# MAGNEBOT2.net
KiCad netlist of a schematic drawn in EAGLE
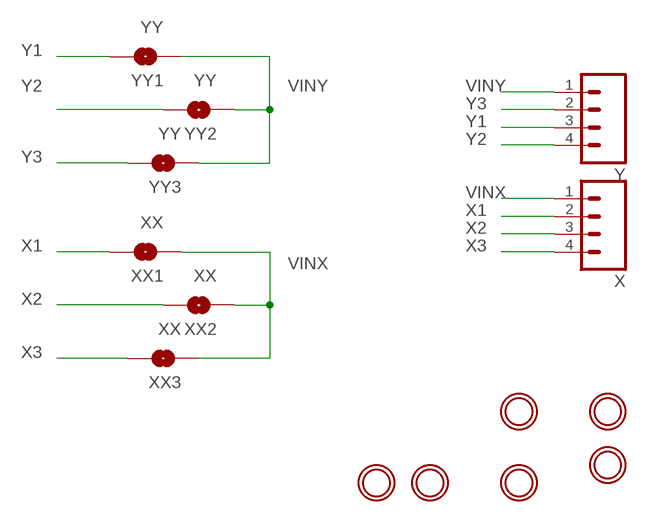
[diagram p0: schematic, sheet 1]

(export (version "E")
  (design (tool "Eeschema 10.0.6"))
  (components
    (comp (ref "U$1")
      (value "MOUNTINGHOLE2.0")
      (footprint "eagle-import:MOUNTINGHOLE_2.0_PLATED")
      (libsource (lib "eagle-import") (part "MOUNTINGHOLE2.0"))
    )
    (comp (ref "U$2")
      (value "MOUNTINGHOLE2.0")
      (footprint "eagle-import:MOUNTINGHOLE_2.0_PLATED")
      (libsource (lib "eagle-import") (part "MOUNTINGHOLE2.0"))
    )
    (comp (ref "U$3")
      (value "MOUNTINGHOLE2.0")
      (footprint "eagle-import:MOUNTINGHOLE_2.0_PLATED")
      (libsource (lib "eagle-import") (part "MOUNTINGHOLE2.0"))
    )
    (comp (ref "U$4")
      (value "MOUNTINGHOLE2.0")
      (footprint "eagle-import:MOUNTINGHOLE_2.0_PLATED")
      (libsource (lib "eagle-import") (part "MOUNTINGHOLE2.0"))
    )
    (comp (ref "U$5")
      (value "MOUNTINGHOLE2.0")
      (footprint "eagle-import:MOUNTINGHOLE_2.0_PLATED")
      (libsource (lib "eagle-import") (part "MOUNTINGHOLE2.0"))
    )
    (comp (ref "U$10")
      (value "MOUNTINGHOLE2.0")
      (footprint "eagle-import:MOUNTINGHOLE_2.0_PLATED")
      (libsource (lib "eagle-import") (part "MOUNTINGHOLE2.0"))
    )
    (comp (ref "X")
      (value "M04PTH")
      (footprint "eagle-import:1X04")
      (libsource (lib "eagle-import") (part "M04PTH"))
    )
    (comp (ref "XX1")
      (value "XX")
      (footprint "eagle-import:SJ_2S-TRACE")
      (libsource (lib "eagle-import") (part "SOLDERJUMPERTRACE"))
    )
    (comp (ref "XX2")
      (value "XX")
      (footprint "eagle-import:SJ_2S-TRACE")
      (libsource (lib "eagle-import") (part "SOLDERJUMPERTRACE"))
    )
    (comp (ref "XX3")
      (value "XX")
      (footprint "eagle-import:SJ_2S-TRACE")
      (libsource (lib "eagle-import") (part "SOLDERJUMPERTRACE"))
    )
    (comp (ref "Y")
      (value "M04PTH")
      (footprint "eagle-import:1X04")
      (libsource (lib "eagle-import") (part "M04PTH"))
    )
    (comp (ref "YY1")
      (value "YY")
      (footprint "eagle-import:SJ_2S-TRACE")
      (libsource (lib "eagle-import") (part "SOLDERJUMPERTRACE"))
    )
    (comp (ref "YY2")
      (value "YY")
      (footprint "eagle-import:SJ_2S-TRACE")
      (libsource (lib "eagle-import") (part "SOLDERJUMPERTRACE"))
    )
    (comp (ref "YY3")
      (value "YY")
      (footprint "eagle-import:SJ_2S-TRACE")
      (libsource (lib "eagle-import") (part "SOLDERJUMPERTRACE"))
    )
  )
  (nets
    (net (code "1") (name "/VINX") (class "Default")
      (node (ref "X") (pin "1") (pinfunction "1_1") (pintype "passive"))
      (node (ref "XX1") (pin "1") (pinfunction "1_1") (pintype "passive"))
      (node (ref "XX2") (pin "1") (pinfunction "1_1") (pintype "passive"))
      (node (ref "XX3") (pin "1") (pinfunction "1_1") (pintype "passive"))
    )
    (net (code "2") (name "/VINY") (class "Default")
      (node (ref "Y") (pin "1") (pinfunction "1_1") (pintype "passive"))
      (node (ref "YY1") (pin "1") (pinfunction "1_1") (pintype "passive"))
      (node (ref "YY2") (pin "1") (pinfunction "1_1") (pintype "passive"))
      (node (ref "YY3") (pin "1") (pinfunction "1_1") (pintype "passive"))
    )
    (net (code "3") (name "/X1") (class "Default")
      (node (ref "X") (pin "2") (pinfunction "2_2") (pintype "passive"))
      (node (ref "XX1") (pin "2") (pinfunction "2_2") (pintype "passive"))
    )
    (net (code "4") (name "/X2") (class "Default")
      (node (ref "X") (pin "3") (pinfunction "3_3") (pintype "passive"))
      (node (ref "XX2") (pin "2") (pinfunction "2_2") (pintype "passive"))
    )
    (net (code "5") (name "/X3") (class "Default")
      (node (ref "X") (pin "4") (pinfunction "4_4") (pintype "passive"))
      (node (ref "XX3") (pin "2") (pinfunction "2_2") (pintype "passive"))
    )
    (net (code "6") (name "/Y1") (class "Default")
      (node (ref "Y") (pin "3") (pinfunction "3_3") (pintype "passive"))
      (node (ref "YY1") (pin "2") (pinfunction "2_2") (pintype "passive"))
    )
    (net (code "7") (name "/Y2") (class "Default")
      (node (ref "Y") (pin "4") (pinfunction "4_4") (pintype "passive"))
      (node (ref "YY2") (pin "2") (pinfunction "2_2") (pintype "passive"))
    )
    (net (code "8") (name "/Y3") (class "Default")
      (node (ref "Y") (pin "2") (pinfunction "2_2") (pintype "passive"))
      (node (ref "YY3") (pin "2") (pinfunction "2_2") (pintype "passive"))
    )
  )
)
